# LEDs.net
KiCad netlist of a schematic drawn in Altium Designer
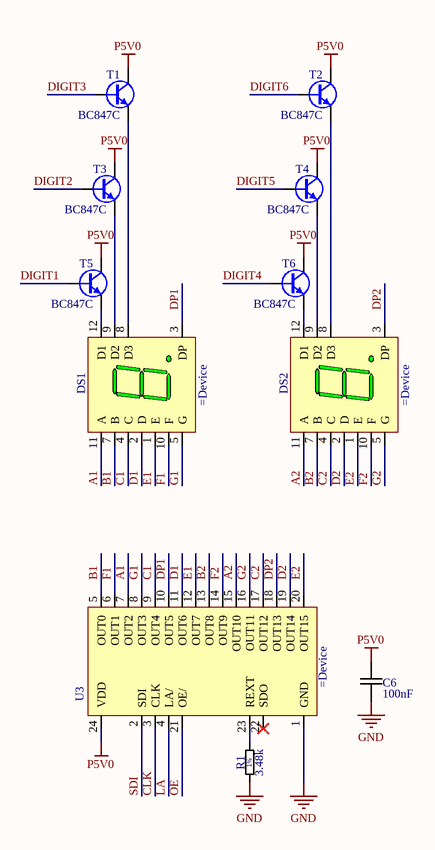
[diagram p0: LEDs.SchDoc]

(export (version "E")
  (design (tool "Eeschema 10.0.6"))
  (components
    (comp (ref "C6")
      (value "100nF")
      (footprint "CAPC0402X60N")
      (description "Non-polarised capacitor")
      (fields
        (field (name "MANUFACTURER") "GENERIC")
        (field (name "MANUFACTURER PART NUMBER") "CC0402_100NF_16V_10%_X7R")
        (field (name "AUTHOR") "KB")
      )
      (libsource (lib "Capacitors") (part "Capacitor - non polarized"))
    )
    (comp (ref "DS1")
      (value "~")
      (footprint "7seg_3digits")
      (description "7-seg LED Display; 9.14mm; 0.36ˇ¨; 3 Digits; Green")
      (fields
        (field (name "MANUFACTURER") "Generic")
        (field (name "MANUFACTURER 1 PART NUMBER") "LTD036BAG-101A-02")
        (field (name "AUTHOR") "JK")
      )
      (libsource (lib "ICs And Semiconductors") (part "7-Segment Green Display CA 3-Digits"))
    )
    (comp (ref "DS2")
      (value "~")
      (footprint "7seg_3digits")
      (description "7-seg LED Display; 9.14mm; 0.36ˇ¨; 3 Digits; Green")
      (fields
        (field (name "MANUFACTURER") "Generic")
        (field (name "MANUFACTURER 1 PART NUMBER") "LTD036BAG-101A-02")
        (field (name "AUTHOR") "JK")
      )
      (libsource (lib "ICs And Semiconductors") (part "7-Segment Green Display CA 3-Digits"))
    )
    (comp (ref "R1")
      (value "3.48k")
      (footprint "RESC0402X40N")
      (description "General Purpose Thick Film Chip Resistor")
      (fields
        (field (name "MANUFACTURER") "GENERIC")
        (field (name "MANUFACTURER PART NUMBER") "R0402_3K48_0.0625W 0.1W 0.125W 0.25W 0.5W 1W 0.75W 1W_100PPM")
        (field (name "AUTHOR") "KB")
      )
      (libsource (lib "Resistors") (part "Resistor - 1%"))
    )
    (comp (ref "T1")
      (value "BC847C")
      (footprint "SOT23-3")
      (description "NPN Bipolar Transistor, 45V, 100mA, 250mW, SOT23")
      (fields (field (name "MANUFACTURER 1 PART NUMBER") "BC847C.215") (field (name "AUTHOR") "KB"))
      (libsource (lib "ICs And Semiconductors") (part "NPN B1 E2 C3"))
    )
    (comp (ref "T2")
      (value "BC847C")
      (footprint "SOT23-3")
      (description "NPN Bipolar Transistor, 45V, 100mA, 250mW, SOT23")
      (fields (field (name "MANUFACTURER 1 PART NUMBER") "BC847C.215") (field (name "AUTHOR") "KB"))
      (libsource (lib "ICs And Semiconductors") (part "NPN B1 E2 C3"))
    )
    (comp (ref "T3")
      (value "BC847C")
      (footprint "SOT23-3")
      (description "NPN Bipolar Transistor, 45V, 100mA, 250mW, SOT23")
      (fields (field (name "MANUFACTURER 1 PART NUMBER") "BC847C.215") (field (name "AUTHOR") "KB"))
      (libsource (lib "ICs And Semiconductors") (part "NPN B1 E2 C3"))
    )
    (comp (ref "T4")
      (value "BC847C")
      (footprint "SOT23-3")
      (description "NPN Bipolar Transistor, 45V, 100mA, 250mW, SOT23")
      (fields (field (name "MANUFACTURER 1 PART NUMBER") "BC847C.215") (field (name "AUTHOR") "KB"))
      (libsource (lib "ICs And Semiconductors") (part "NPN B1 E2 C3"))
    )
    (comp (ref "T5")
      (value "BC847C")
      (footprint "SOT23-3")
      (description "NPN Bipolar Transistor, 45V, 100mA, 250mW, SOT23")
      (fields (field (name "MANUFACTURER 1 PART NUMBER") "BC847C.215") (field (name "AUTHOR") "KB"))
      (libsource (lib "ICs And Semiconductors") (part "NPN B1 E2 C3"))
    )
    (comp (ref "T6")
      (value "BC847C")
      (footprint "SOT23-3")
      (description "NPN Bipolar Transistor, 45V, 100mA, 250mW, SOT23")
      (fields (field (name "MANUFACTURER 1 PART NUMBER") "BC847C.215") (field (name "AUTHOR") "KB"))
      (libsource (lib "ICs And Semiconductors") (part "NPN B1 E2 C3"))
    )
    (comp (ref "U3")
      (value "~")
      (footprint "SOP-24_N")
      (description "Driver, kontroler LED, 5ˇĹ0mA, Kanały: 16, 3ˇĹ,5V, SOP24")
      (fields
        (field (name "MANUFACTURER") "Generic")
        (field (name "MANUFACTURER 1 PART NUMBER") "SCT2024CSOG")
        (field (name "AUTHOR") "UN")
      )
      (libsource (lib "ICs And Semiconductors") (part "SCT2024"))
    )
  )
  (nets
    (net (code "1") (name "/A1") (class "Default")
      (node (ref "DS1") (pin "11") (pinfunction "A_11") (pintype "passive"))
      (node (ref "U3") (pin "7") (pinfunction "OUT2_7") (pintype "passive"))
    )
    (net (code "2") (name "/A2") (class "Default")
      (node (ref "DS2") (pin "11") (pinfunction "A_11") (pintype "passive"))
      (node (ref "U3") (pin "15") (pinfunction "OUT10_15") (pintype "passive"))
    )
    (net (code "3") (name "/B1") (class "Default")
      (node (ref "DS1") (pin "7") (pinfunction "B_7") (pintype "passive"))
      (node (ref "U3") (pin "5") (pinfunction "OUT0_5") (pintype "passive"))
    )
    (net (code "4") (name "/B2") (class "Default")
      (node (ref "DS2") (pin "7") (pinfunction "B_7") (pintype "passive"))
      (node (ref "U3") (pin "13") (pinfunction "OUT8_13") (pintype "passive"))
    )
    (net (code "5") (name "/C1") (class "Default")
      (node (ref "DS1") (pin "4") (pinfunction "C_4") (pintype "passive"))
      (node (ref "U3") (pin "9") (pinfunction "OUT4_9") (pintype "passive"))
    )
    (net (code "6") (name "/C2") (class "Default")
      (node (ref "DS2") (pin "4") (pinfunction "C_4") (pintype "passive"))
      (node (ref "U3") (pin "17") (pinfunction "OUT12_17") (pintype "passive"))
    )
    (net (code "7") (name "/CLK") (class "Default")
      (node (ref "U3") (pin "3") (pinfunction "CLK_3") (pintype "passive"))
    )
    (net (code "8") (name "/D1") (class "Default")
      (node (ref "DS1") (pin "2") (pinfunction "D_2") (pintype "passive"))
      (node (ref "U3") (pin "11") (pinfunction "OUT6_11") (pintype "passive"))
    )
    (net (code "9") (name "/D2") (class "Default")
      (node (ref "DS2") (pin "2") (pinfunction "D_2") (pintype "passive"))
      (node (ref "U3") (pin "19") (pinfunction "OUT14_19") (pintype "passive"))
    )
    (net (code "10") (name "/DIGIT1") (class "Default")
      (node (ref "T5") (pin "1") (pinfunction "B_1") (pintype "passive"))
    )
    (net (code "11") (name "/DIGIT2") (class "Default")
      (node (ref "T3") (pin "1") (pinfunction "B_1") (pintype "passive"))
    )
    (net (code "12") (name "/DIGIT3") (class "Default")
      (node (ref "T1") (pin "1") (pinfunction "B_1") (pintype "passive"))
    )
    (net (code "13") (name "/DIGIT4") (class "Default")
      (node (ref "T6") (pin "1") (pinfunction "B_1") (pintype "passive"))
    )
    (net (code "14") (name "/DIGIT5") (class "Default")
      (node (ref "T4") (pin "1") (pinfunction "B_1") (pintype "passive"))
    )
    (net (code "15") (name "/DIGIT6") (class "Default")
      (node (ref "T2") (pin "1") (pinfunction "B_1") (pintype "passive"))
    )
    (net (code "16") (name "/DP1") (class "Default")
      (node (ref "DS1") (pin "3") (pinfunction "DP_3") (pintype "passive"))
      (node (ref "U3") (pin "10") (pinfunction "OUT5_10") (pintype "passive"))
    )
    (net (code "17") (name "/DP2") (class "Default")
      (node (ref "DS2") (pin "3") (pinfunction "DP_3") (pintype "passive"))
      (node (ref "U3") (pin "18") (pinfunction "OUT13_18") (pintype "passive"))
    )
    (net (code "18") (name "/E1") (class "Default")
      (node (ref "DS1") (pin "1") (pinfunction "E_1") (pintype "passive"))
      (node (ref "U3") (pin "12") (pinfunction "OUT7_12") (pintype "passive"))
    )
    (net (code "19") (name "/E2") (class "Default")
      (node (ref "DS2") (pin "1") (pinfunction "E_1") (pintype "passive"))
      (node (ref "U3") (pin "20") (pinfunction "OUT15_20") (pintype "passive"))
    )
    (net (code "20") (name "/F1") (class "Default")
      (node (ref "DS1") (pin "10") (pinfunction "F_10") (pintype "passive"))
      (node (ref "U3") (pin "6") (pinfunction "OUT1_6") (pintype "passive"))
    )
    (net (code "21") (name "/F2") (class "Default")
      (node (ref "DS2") (pin "10") (pinfunction "F_10") (pintype "passive"))
      (node (ref "U3") (pin "14") (pinfunction "OUT9_14") (pintype "passive"))
    )
    (net (code "22") (name "/G1") (class "Default")
      (node (ref "DS1") (pin "5") (pinfunction "G_5") (pintype "passive"))
      (node (ref "U3") (pin "8") (pinfunction "OUT3_8") (pintype "passive"))
    )
    (net (code "23") (name "/G2") (class "Default")
      (node (ref "DS2") (pin "5") (pinfunction "G_5") (pintype "passive"))
      (node (ref "U3") (pin "16") (pinfunction "OUT11_16") (pintype "passive"))
    )
    (net (code "24") (name "/LA") (class "Default")
      (node (ref "U3") (pin "4") (pinfunction "LA/_4") (pintype "passive"))
    )
    (net (code "25") (name "/OE") (class "Default")
      (node (ref "U3") (pin "21") (pinfunction "OE/_21") (pintype "passive"))
    )
    (net (code "26") (name "/SDI") (class "Default")
      (node (ref "U3") (pin "2") (pinfunction "SDI_2") (pintype "passive"))
    )
    (net (code "27") (name "GND") (class "Default")
      (node (ref "C6") (pin "1") (pinfunction "1_1") (pintype "passive"))
      (node (ref "R1") (pin "1") (pinfunction "1_1") (pintype "passive"))
      (node (ref "U3") (pin "1") (pinfunction "GND_1") (pintype "power_in"))
    )
    (net (code "28") (name "Net-(DS1-D1)") (class "Default")
      (node (ref "DS1") (pin "12") (pinfunction "D1_12") (pintype "passive"))
      (node (ref "T5") (pin "2") (pinfunction "E_2") (pintype "passive"))
    )
    (net (code "29") (name "Net-(DS1-D2)") (class "Default")
      (node (ref "DS1") (pin "9") (pinfunction "D2_9") (pintype "passive"))
      (node (ref "T3") (pin "2") (pinfunction "E_2") (pintype "passive"))
    )
    (net (code "30") (name "Net-(DS1-D3)") (class "Default")
      (node (ref "DS1") (pin "8") (pinfunction "D3_8") (pintype "passive"))
      (node (ref "T1") (pin "2") (pinfunction "E_2") (pintype "passive"))
    )
    (net (code "31") (name "Net-(DS2-D1)") (class "Default")
      (node (ref "DS2") (pin "12") (pinfunction "D1_12") (pintype "passive"))
      (node (ref "T6") (pin "2") (pinfunction "E_2") (pintype "passive"))
    )
    (net (code "32") (name "Net-(DS2-D2)") (class "Default")
      (node (ref "DS2") (pin "9") (pinfunction "D2_9") (pintype "passive"))
      (node (ref "T4") (pin "2") (pinfunction "E_2") (pintype "passive"))
    )
    (net (code "33") (name "Net-(DS2-D3)") (class "Default")
      (node (ref "DS2") (pin "8") (pinfunction "D3_8") (pintype "passive"))
      (node (ref "T2") (pin "2") (pinfunction "E_2") (pintype "passive"))
    )
    (net (code "34") (name "Net-(U3-REXT)") (class "Default")
      (node (ref "R1") (pin "2") (pinfunction "2_2") (pintype "passive"))
      (node (ref "U3") (pin "23") (pinfunction "REXT_23") (pintype "passive"))
    )
    (net (code "35") (name "P5V0") (class "Default")
      (node (ref "C6") (pin "2") (pinfunction "2_2") (pintype "passive"))
      (node (ref "T1") (pin "3") (pinfunction "C_3") (pintype "passive"))
      (node (ref "T2") (pin "3") (pinfunction "C_3") (pintype "passive"))
      (node (ref "T3") (pin "3") (pinfunction "C_3") (pintype "passive"))
      (node (ref "T4") (pin "3") (pinfunction "C_3") (pintype "passive"))
      (node (ref "T5") (pin "3") (pinfunction "C_3") (pintype "passive"))
      (node (ref "T6") (pin "3") (pinfunction "C_3") (pintype "passive"))
      (node (ref "U3") (pin "24") (pinfunction "VDD_24") (pintype "power_in"))
    )
    (net (code "36") (name "unconnected-(U3-SDO-Pad22)") (class "Default")
      (node (ref "U3") (pin "22") (pinfunction "SDO_22") (pintype "passive+no_connect"))
    )
  )
)
